# powersupply_example.net
KiCad netlist of a schematic drawn in EAGLE
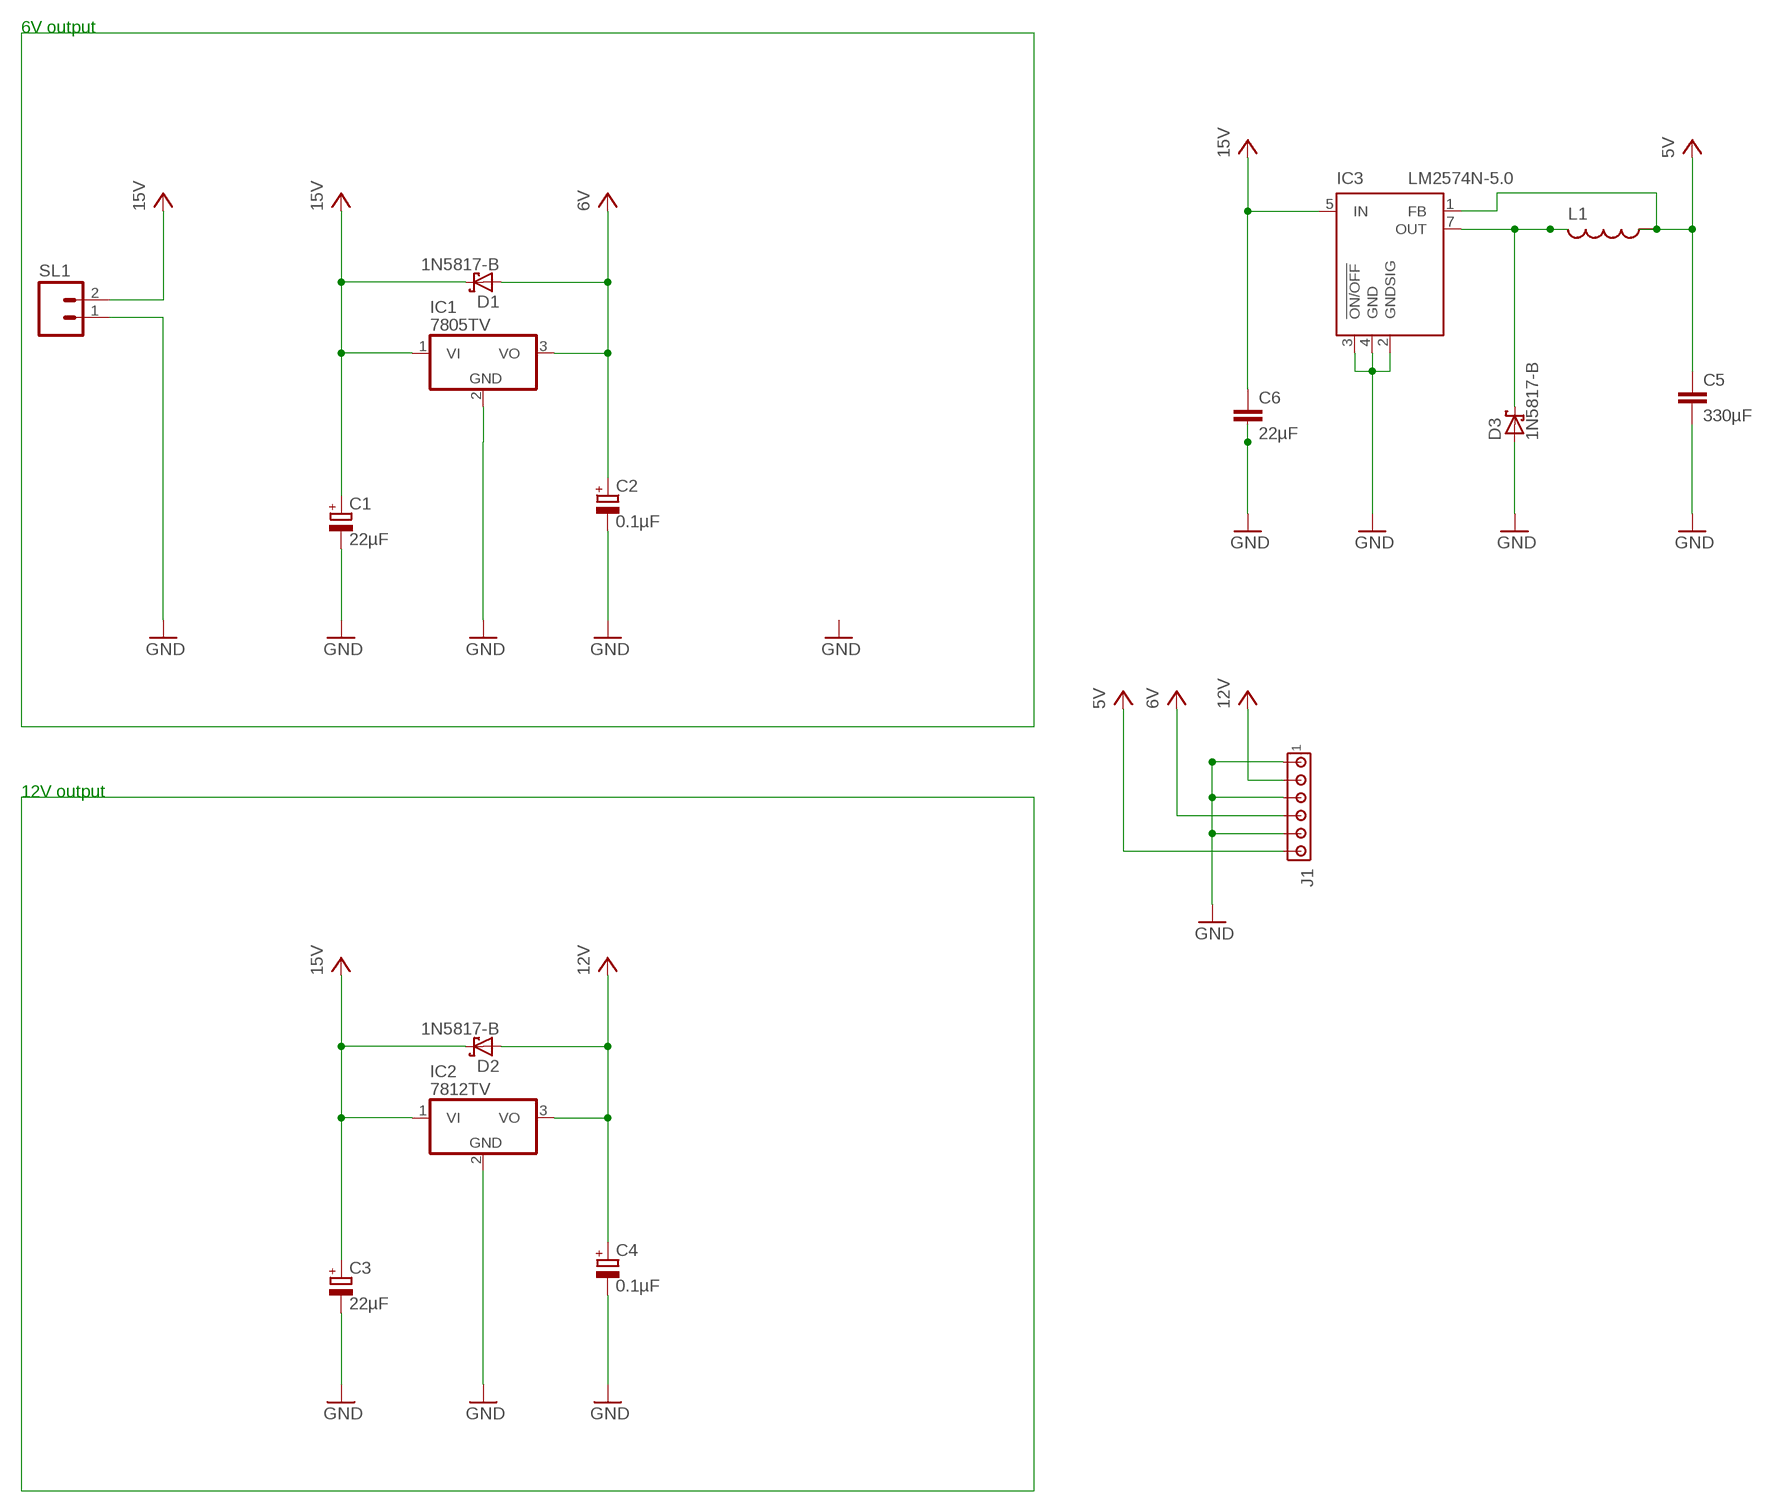
[diagram p0: schematic, sheet 1]

(export (version "E")
  (design (tool "Eeschema 10.0.6"))
  (components
    (comp (ref "C1")
      (value "22µF")
      (footprint "eagle-import:E2,5-5")
      (libsource (lib "eagle-import") (part "CPOL-EUE2.5-5"))
    )
    (comp (ref "C2")
      (value "0.1µF")
      (footprint "eagle-import:E2,5-5")
      (libsource (lib "eagle-import") (part "CPOL-EUE2.5-5"))
    )
    (comp (ref "C3")
      (value "22µF")
      (footprint "eagle-import:E2,5-5")
      (libsource (lib "eagle-import") (part "CPOL-EUE2.5-5"))
    )
    (comp (ref "C4")
      (value "0.1µF")
      (footprint "eagle-import:E2,5-5")
      (libsource (lib "eagle-import") (part "CPOL-EUE2.5-5"))
    )
    (comp (ref "C5")
      (value "330µF")
      (footprint "eagle-import:C025-040X050")
      (libsource (lib "eagle-import") (part "C-EU025-040X050"))
    )
    (comp (ref "C6")
      (value "22µF")
      (footprint "eagle-import:C025-040X050")
      (libsource (lib "eagle-import") (part "C-EU025-040X050"))
    )
    (comp (ref "D1")
      (value "1N5817-B")
      (footprint "eagle-import:DO41-7.6")
      (libsource (lib "eagle-import") (part "1N5817-B"))
    )
    (comp (ref "D2")
      (value "1N5817-B")
      (footprint "eagle-import:DO41-7.6")
      (libsource (lib "eagle-import") (part "1N5817-B"))
    )
    (comp (ref "D3")
      (value "1N5817-B")
      (footprint "eagle-import:DO41-7.6")
      (libsource (lib "eagle-import") (part "1N5817-B"))
    )
    (comp (ref "IC1")
      (value "7805TV")
      (footprint "eagle-import:TO220V")
      (libsource (lib "eagle-import") (part "78TV05"))
    )
    (comp (ref "IC2")
      (value "7812TV")
      (footprint "eagle-import:TO220V")
      (libsource (lib "eagle-import") (part "78TV12"))
    )
    (comp (ref "IC3")
      (value "LM2574N-5.0")
      (footprint "eagle-import:DIL08")
      (libsource (lib "eagle-import") (part "LM2574?-N5.0"))
    )
    (comp (ref "J1")
      (value "MTA06-100")
      (footprint "eagle-import:10X06MTA")
      (libsource (lib "eagle-import") (part "MTA06-100"))
    )
    (comp (ref "L1")
      (value "L-US0204/7")
      (footprint "eagle-import:0204_7")
      (libsource (lib "eagle-import") (part "L-US0204/7"))
    )
    (comp (ref "SL1")
      (value "M02")
      (footprint "eagle-import:02P")
      (libsource (lib "eagle-import") (part "M02"))
    )
  )
  (nets
    (net (code "1") (name "5V") (class "Default")
      (node (ref "C5") (pin "1") (pinfunction "1_1") (pintype "passive"))
      (node (ref "IC3") (pin "1") (pinfunction "FB_1") (pintype "input"))
      (node (ref "J1") (pin "6") (pinfunction "6_6") (pintype "passive"))
      (node (ref "L1") (pin "1") (pinfunction "1_1") (pintype "passive"))
    )
    (net (code "2") (name "6V") (class "Default")
      (node (ref "C2") (pin "+") (pinfunction "+_+") (pintype "passive"))
      (node (ref "D1") (pin "A") (pinfunction "A_A") (pintype "passive"))
      (node (ref "IC1") (pin "3") (pinfunction "VO_3") (pintype "passive"))
      (node (ref "J1") (pin "4") (pinfunction "4_4") (pintype "passive"))
    )
    (net (code "3") (name "12V") (class "Default")
      (node (ref "C4") (pin "+") (pinfunction "+_+") (pintype "passive"))
      (node (ref "D2") (pin "A") (pinfunction "A_A") (pintype "passive"))
      (node (ref "IC2") (pin "3") (pinfunction "VO_3") (pintype "passive"))
      (node (ref "J1") (pin "2") (pinfunction "2_2") (pintype "passive"))
    )
    (net (code "4") (name "15V") (class "Default")
      (node (ref "C1") (pin "+") (pinfunction "+_+") (pintype "passive"))
      (node (ref "C3") (pin "+") (pinfunction "+_+") (pintype "passive"))
      (node (ref "C6") (pin "1") (pinfunction "1_1") (pintype "passive"))
      (node (ref "D1") (pin "C") (pinfunction "C_C") (pintype "passive"))
      (node (ref "D2") (pin "C") (pinfunction "C_C") (pintype "passive"))
      (node (ref "IC1") (pin "1") (pinfunction "VI_1") (pintype "input"))
      (node (ref "IC2") (pin "1") (pinfunction "VI_1") (pintype "input"))
      (node (ref "IC3") (pin "5") (pinfunction "IN_5") (pintype "input"))
      (node (ref "SL1") (pin "2") (pinfunction "2_2") (pintype "passive"))
    )
    (net (code "5") (name "GND") (class "Default")
      (node (ref "C1") (pin "-") (pinfunction "-_-") (pintype "passive"))
      (node (ref "C2") (pin "-") (pinfunction "-_-") (pintype "passive"))
      (node (ref "C3") (pin "-") (pinfunction "-_-") (pintype "passive"))
      (node (ref "C4") (pin "-") (pinfunction "-_-") (pintype "passive"))
      (node (ref "C5") (pin "2") (pinfunction "2_2") (pintype "passive"))
      (node (ref "C6") (pin "2") (pinfunction "2_2") (pintype "passive"))
      (node (ref "D3") (pin "A") (pinfunction "A_A") (pintype "passive"))
      (node (ref "IC1") (pin "2") (pinfunction "GND_2") (pintype "passive"))
      (node (ref "IC2") (pin "2") (pinfunction "GND_2") (pintype "passive"))
      (node (ref "IC3") (pin "2") (pinfunction "GNDSIG_2") (pintype "input"))
      (node (ref "IC3") (pin "3") (pinfunction "~{ON/OFF}_3") (pintype "input"))
      (node (ref "IC3") (pin "4") (pinfunction "GND_4") (pintype "power_in"))
      (node (ref "J1") (pin "1") (pinfunction "1_1") (pintype "passive"))
      (node (ref "J1") (pin "3") (pinfunction "3_3") (pintype "passive"))
      (node (ref "J1") (pin "5") (pinfunction "5_5") (pintype "passive"))
      (node (ref "SL1") (pin "1") (pinfunction "1_1") (pintype "passive"))
    )
    (net (code "6") (name "Net-(IC3-OUT)") (class "Default")
      (node (ref "D3") (pin "C") (pinfunction "C_C") (pintype "passive"))
      (node (ref "IC3") (pin "7") (pinfunction "OUT_7") (pintype "passive"))
      (node (ref "L1") (pin "2") (pinfunction "2_2") (pintype "passive"))
    )
  )
)
